# dimmer.net
KiCad netlist of a schematic drawn in EAGLE
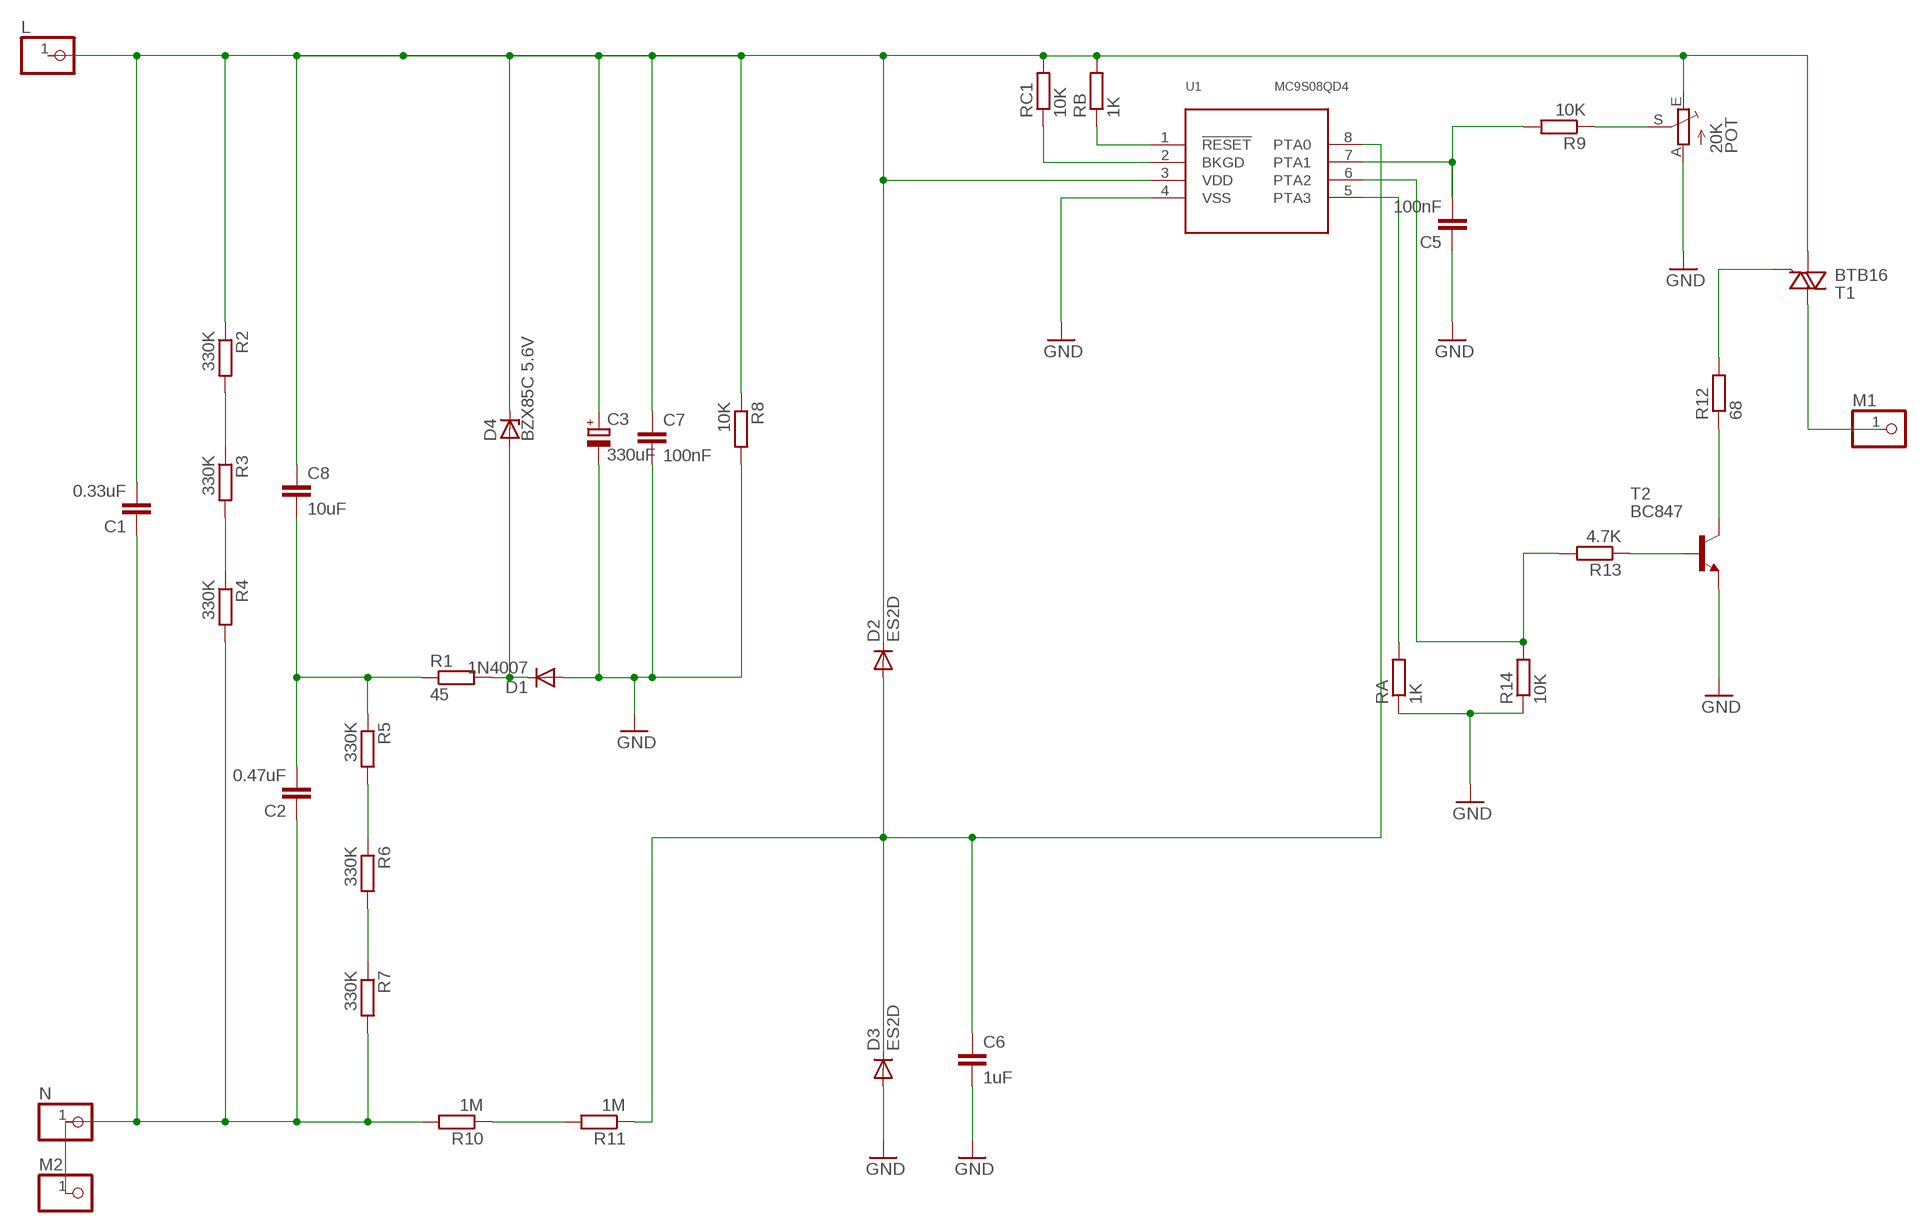
[diagram p0: schematic, sheet 1]

(export (version "E")
  (design (tool "Eeschema 10.0.6"))
  (components
    (comp (ref "C1")
      (value "0.33uF")
      (footprint "eagle-import:C075-032X103")
      (libsource (lib "eagle-import") (part "C-EU075-032X103"))
    )
    (comp (ref "C2")
      (value "0.47uF")
      (footprint "eagle-import:C075-032X103")
      (libsource (lib "eagle-import") (part "C-EU075-032X103"))
    )
    (comp (ref "C3")
      (value "330uF")
      (footprint "eagle-import:E5-5")
      (libsource (lib "eagle-import") (part "CPOL-EUE5-5"))
    )
    (comp (ref "C5")
      (value "100nF")
      (footprint "eagle-import:C1210")
      (libsource (lib "eagle-import") (part "C-EUC1210"))
    )
    (comp (ref "C6")
      (value "1uF")
      (footprint "eagle-import:C1210")
      (libsource (lib "eagle-import") (part "C-EUC1210"))
    )
    (comp (ref "C7")
      (value "100nF")
      (footprint "eagle-import:C1210")
      (libsource (lib "eagle-import") (part "C-EUC1210"))
    )
    (comp (ref "C8")
      (value "10uF")
      (footprint "eagle-import:C1210")
      (libsource (lib "eagle-import") (part "C-EUC1210"))
    )
    (comp (ref "D1")
      (value "1N4007")
      (footprint "eagle-import:DO41-10")
      (libsource (lib "eagle-import") (part "1N4004"))
    )
    (comp (ref "D2")
      (value "ES2D")
      (footprint "eagle-import:SMB")
      (libsource (lib "eagle-import") (part "ES2D"))
    )
    (comp (ref "D3")
      (value "ES2D")
      (footprint "eagle-import:SMB")
      (libsource (lib "eagle-import") (part "ES2D"))
    )
    (comp (ref "D4")
      (value "BZX85C 5.6V")
      (footprint "eagle-import:DO35Z10")
      (libsource (lib "eagle-import") (part "ZTK"))
    )
    (comp (ref "L")
      (value "PINHD-1X1")
      (footprint "eagle-import:1X01")
      (libsource (lib "eagle-import") (part "PINHD-1X1"))
    )
    (comp (ref "M1")
      (value "PINHD-1X1")
      (footprint "eagle-import:1X01")
      (libsource (lib "eagle-import") (part "PINHD-1X1"))
    )
    (comp (ref "M2")
      (value "PINHD-1X1")
      (footprint "eagle-import:1X01")
      (libsource (lib "eagle-import") (part "PINHD-1X1"))
    )
    (comp (ref "N")
      (value "PINHD-1X1")
      (footprint "eagle-import:1X01")
      (libsource (lib "eagle-import") (part "PINHD-1X1"))
    )
    (comp (ref "POT")
      (value "20K")
      (footprint "eagle-import:PT-10")
      (libsource (lib "eagle-import") (part "TRIM_EU-PT10"))
    )
    (comp (ref "R1")
      (value "45")
      (footprint "eagle-import:0207_10")
      (libsource (lib "eagle-import") (part "R-EU_0207/10"))
    )
    (comp (ref "R2")
      (value "330K")
      (footprint "eagle-import:R1210")
      (libsource (lib "eagle-import") (part "R-EU_R1210"))
    )
    (comp (ref "R3")
      (value "330K")
      (footprint "eagle-import:R1210")
      (libsource (lib "eagle-import") (part "R-EU_R1210"))
    )
    (comp (ref "R4")
      (value "330K")
      (footprint "eagle-import:R1210")
      (libsource (lib "eagle-import") (part "R-EU_R1210"))
    )
    (comp (ref "R5")
      (value "330K")
      (footprint "eagle-import:R1210")
      (libsource (lib "eagle-import") (part "R-EU_R1210"))
    )
    (comp (ref "R6")
      (value "330K")
      (footprint "eagle-import:R1210")
      (libsource (lib "eagle-import") (part "R-EU_R1210"))
    )
    (comp (ref "R7")
      (value "330K")
      (footprint "eagle-import:R1210")
      (libsource (lib "eagle-import") (part "R-EU_R1210"))
    )
    (comp (ref "R8")
      (value "10K")
      (footprint "eagle-import:R1210")
      (libsource (lib "eagle-import") (part "R-EU_R1210"))
    )
    (comp (ref "R9")
      (value "10K")
      (footprint "eagle-import:R1210")
      (libsource (lib "eagle-import") (part "R-EU_R1210"))
    )
    (comp (ref "R10")
      (value "1M")
      (footprint "eagle-import:R1210")
      (libsource (lib "eagle-import") (part "R-EU_R1210"))
    )
    (comp (ref "R11")
      (value "1M")
      (footprint "eagle-import:R1210")
      (libsource (lib "eagle-import") (part "R-EU_R1210"))
    )
    (comp (ref "R12")
      (value "68")
      (footprint "eagle-import:R1210")
      (libsource (lib "eagle-import") (part "R-EU_R1210"))
    )
    (comp (ref "R13")
      (value "4.7K")
      (footprint "eagle-import:R1210")
      (libsource (lib "eagle-import") (part "R-EU_R1210"))
    )
    (comp (ref "R14")
      (value "10K")
      (footprint "eagle-import:R1210")
      (libsource (lib "eagle-import") (part "R-EU_R1210"))
    )
    (comp (ref "RA")
      (value "1K")
      (footprint "eagle-import:R1210")
      (libsource (lib "eagle-import") (part "R-EU_R1210"))
    )
    (comp (ref "RB")
      (value "1K")
      (footprint "eagle-import:R1210")
      (libsource (lib "eagle-import") (part "R-EU_R1210"))
    )
    (comp (ref "RC1")
      (value "10K")
      (footprint "eagle-import:R1210")
      (libsource (lib "eagle-import") (part "R-EU_R1210"))
    )
    (comp (ref "T1")
      (value "BTB16")
      (footprint "eagle-import:TO218DS")
      (libsource (lib "eagle-import") (part "TIC253"))
    )
    (comp (ref "T2")
      (value "BC847")
      (footprint "eagle-import:SOT23")
      (libsource (lib "eagle-import") (part "BC847SMDA"))
    )
    (comp (ref "U1")
      (value "MC9S08QD4")
      (footprint "eagle-import:MC9S08QD4")
      (libsource (lib "eagle-import") (part "MC9S08QD4"))
    )
  )
  (nets
    (net (code "1") (name "GND") (class "Default")
      (node (ref "C3") (pin "-") (pinfunction "-_-") (pintype "passive"))
      (node (ref "C5") (pin "1") (pinfunction "1_1") (pintype "passive"))
      (node (ref "C6") (pin "2") (pinfunction "2_2") (pintype "passive"))
      (node (ref "C7") (pin "2") (pinfunction "2_2") (pintype "passive"))
      (node (ref "D1") (pin "A") (pinfunction "A_A") (pintype "passive"))
      (node (ref "D3") (pin "A") (pinfunction "A_A") (pintype "passive"))
      (node (ref "POT") (pin "A") (pinfunction "A_A") (pintype "passive"))
      (node (ref "R14") (pin "1") (pinfunction "1_1") (pintype "passive"))
      (node (ref "R8") (pin "2") (pinfunction "2_2") (pintype "passive"))
      (node (ref "RA") (pin "1") (pinfunction "1_1") (pintype "passive"))
      (node (ref "T2") (pin "2") (pinfunction "E_2") (pintype "passive"))
      (node (ref "U1") (pin "4") (pinfunction "VSS_4") (pintype "bidirectional"))
    )
    (net (code "2") (name "Net-(C1-Pad1)") (class "Default")
      (node (ref "C1") (pin "1") (pinfunction "1_1") (pintype "passive"))
      (node (ref "C2") (pin "1") (pinfunction "1_1") (pintype "passive"))
      (node (ref "M2") (pin "1") (pinfunction "1_1") (pintype "passive"))
      (node (ref "N") (pin "1") (pinfunction "1_1") (pintype "passive"))
      (node (ref "R10") (pin "2") (pinfunction "2_2") (pintype "passive"))
      (node (ref "R4") (pin "2") (pinfunction "2_2") (pintype "passive"))
      (node (ref "R7") (pin "2") (pinfunction "2_2") (pintype "passive"))
    )
    (net (code "3") (name "Net-(C2-Pad2)") (class "Default")
      (node (ref "C2") (pin "2") (pinfunction "2_2") (pintype "passive"))
      (node (ref "C8") (pin "2") (pinfunction "2_2") (pintype "passive"))
      (node (ref "R1") (pin "1") (pinfunction "1_1") (pintype "passive"))
      (node (ref "R5") (pin "1") (pinfunction "1_1") (pintype "passive"))
    )
    (net (code "4") (name "Net-(D1-PadC)") (class "Default")
      (node (ref "D1") (pin "C") (pinfunction "C_C") (pintype "passive"))
      (node (ref "D4") (pin "A") (pinfunction "A_A") (pintype "passive"))
      (node (ref "R1") (pin "2") (pinfunction "2_2") (pintype "passive"))
    )
    (net (code "5") (name "Net-(M1-Pad1)") (class "Default")
      (node (ref "M1") (pin "1") (pinfunction "1_1") (pintype "passive"))
      (node (ref "T1") (pin "A2") (pinfunction "A2_A2") (pintype "passive"))
    )
    (net (code "6") (name "Net-(POT-PadS)") (class "Default")
      (node (ref "POT") (pin "S") (pinfunction "S_S") (pintype "passive"))
      (node (ref "R9") (pin "1") (pinfunction "1_1") (pintype "passive"))
    )
    (net (code "7") (name "Net-(R2-Pad2)") (class "Default")
      (node (ref "R2") (pin "2") (pinfunction "2_2") (pintype "passive"))
      (node (ref "R3") (pin "1") (pinfunction "1_1") (pintype "passive"))
    )
    (net (code "8") (name "Net-(R3-Pad2)") (class "Default")
      (node (ref "R3") (pin "2") (pinfunction "2_2") (pintype "passive"))
      (node (ref "R4") (pin "1") (pinfunction "1_1") (pintype "passive"))
    )
    (net (code "9") (name "Net-(R5-Pad2)") (class "Default")
      (node (ref "R5") (pin "2") (pinfunction "2_2") (pintype "passive"))
      (node (ref "R6") (pin "1") (pinfunction "1_1") (pintype "passive"))
    )
    (net (code "10") (name "Net-(R6-Pad2)") (class "Default")
      (node (ref "R6") (pin "2") (pinfunction "2_2") (pintype "passive"))
      (node (ref "R7") (pin "1") (pinfunction "1_1") (pintype "passive"))
    )
    (net (code "11") (name "Net-(R10-Pad1)") (class "Default")
      (node (ref "R10") (pin "1") (pinfunction "1_1") (pintype "passive"))
      (node (ref "R11") (pin "2") (pinfunction "2_2") (pintype "passive"))
    )
    (net (code "12") (name "Net-(R12-Pad2)") (class "Default")
      (node (ref "R12") (pin "2") (pinfunction "2_2") (pintype "passive"))
      (node (ref "T1") (pin "G") (pinfunction "G_G") (pintype "passive"))
    )
    (net (code "13") (name "Net-(T2-B)") (class "Default")
      (node (ref "R13") (pin "1") (pinfunction "1_1") (pintype "passive"))
      (node (ref "T2") (pin "1") (pinfunction "B_1") (pintype "passive"))
    )
    (net (code "14") (name "Net-(T2-C)") (class "Default")
      (node (ref "R12") (pin "1") (pinfunction "1_1") (pintype "passive"))
      (node (ref "T2") (pin "3") (pinfunction "C_3") (pintype "passive"))
    )
    (net (code "15") (name "Net-(U1-BKGD)") (class "Default")
      (node (ref "RC1") (pin "1") (pinfunction "1_1") (pintype "passive"))
      (node (ref "U1") (pin "2") (pinfunction "BKGD_2") (pintype "bidirectional"))
    )
    (net (code "16") (name "Net-(U1-PTA0)") (class "Default")
      (node (ref "C6") (pin "1") (pinfunction "1_1") (pintype "passive"))
      (node (ref "D2") (pin "A") (pinfunction "A_A") (pintype "passive"))
      (node (ref "D3") (pin "C") (pinfunction "C_C") (pintype "passive"))
      (node (ref "R11") (pin "1") (pinfunction "1_1") (pintype "passive"))
      (node (ref "U1") (pin "8") (pinfunction "PTA0_8") (pintype "bidirectional"))
    )
    (net (code "17") (name "Net-(U1-PTA1)") (class "Default")
      (node (ref "C5") (pin "2") (pinfunction "2_2") (pintype "passive"))
      (node (ref "R9") (pin "2") (pinfunction "2_2") (pintype "passive"))
      (node (ref "U1") (pin "7") (pinfunction "PTA1_7") (pintype "bidirectional"))
    )
    (net (code "18") (name "Net-(U1-PTA2)") (class "Default")
      (node (ref "R13") (pin "2") (pinfunction "2_2") (pintype "passive"))
      (node (ref "R14") (pin "2") (pinfunction "2_2") (pintype "passive"))
      (node (ref "U1") (pin "6") (pinfunction "PTA2_6") (pintype "bidirectional"))
    )
    (net (code "19") (name "Net-(U1-PTA3)") (class "Default")
      (node (ref "RA") (pin "2") (pinfunction "2_2") (pintype "passive"))
      (node (ref "U1") (pin "5") (pinfunction "PTA3_5") (pintype "bidirectional"))
    )
    (net (code "20") (name "Net-(U1-VDD)") (class "Default")
      (node (ref "C1") (pin "2") (pinfunction "2_2") (pintype "passive"))
      (node (ref "C3") (pin "+") (pinfunction "+_+") (pintype "passive"))
      (node (ref "C7") (pin "1") (pinfunction "1_1") (pintype "passive"))
      (node (ref "C8") (pin "1") (pinfunction "1_1") (pintype "passive"))
      (node (ref "D2") (pin "C") (pinfunction "C_C") (pintype "passive"))
      (node (ref "D4") (pin "C") (pinfunction "C_C") (pintype "passive"))
      (node (ref "L") (pin "1") (pinfunction "1_1") (pintype "passive"))
      (node (ref "POT") (pin "E") (pinfunction "E_E") (pintype "passive"))
      (node (ref "R2") (pin "1") (pinfunction "1_1") (pintype "passive"))
      (node (ref "R8") (pin "1") (pinfunction "1_1") (pintype "passive"))
      (node (ref "RB") (pin "2") (pinfunction "2_2") (pintype "passive"))
      (node (ref "RC1") (pin "2") (pinfunction "2_2") (pintype "passive"))
      (node (ref "T1") (pin "A1") (pinfunction "A1_A1") (pintype "passive"))
      (node (ref "U1") (pin "3") (pinfunction "VDD_3") (pintype "bidirectional"))
    )
    (net (code "21") (name "Net-(U1-~{RESET})") (class "Default")
      (node (ref "RB") (pin "1") (pinfunction "1_1") (pintype "passive"))
      (node (ref "U1") (pin "1") (pinfunction "~{RESET}_1") (pintype "bidirectional"))
    )
  )
)
